# Temperature_humidity.net
KiCad netlist of a schematic drawn in Altium Designer
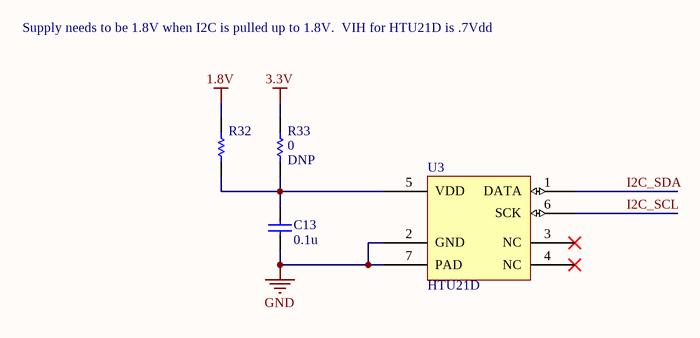
[diagram p0: Temperature_humidity.SchDoc]

(export (version "E")
  (design (tool "Eeschema 10.0.6"))
  (components
    (comp (ref "C13")
      (value "0.1u")
      (footprint "CAP0603")
      (description "CAP CER 0.1UF 50V 10% X7R 0603")
      (fields (field (name "TOLERANCE") "10%") (field (name "VOLTAGE") "50V"))
      (libsource (lib "Morpheus_pill") (part "C_0.1u_10_50_X7R_0603"))
    )
    (comp (ref "R32")
      (value "R_0_jumper_0.1_0402")
      (footprint "RES0402-SENSE-DVT")
      (description "RES SMD 0.0 OHM JUMPER 1/16W")
      (fields (field (name "TOLERANCE") "Jumper") (field (name "POWER") "1/16W"))
      (libsource (lib "Morpheus_pill") (part "R_0_jumper_0.1_0402"))
    )
    (comp (ref "R33")
      (value "DNP")
      (footprint "RES0402-SENSE-DVT")
      (description "RES SMD 0.0 OHM JUMPER 1/16W")
      (fields
        (field (name "ALTIUM_VALUE") "0")
        (field (name "TOLERANCE") "Jumper")
        (field (name "POWER") "1/16W")
      )
      (libsource (lib "Morpheus_pill") (part "R_0_jumper_0.1_0402"))
    )
    (comp (ref "U3")
      (value "HTU21D")
      (footprint "HTU2xx")
      (description "Meas-spec T/H sensor")
      (libsource (lib "Morpheus_pill") (part "HTU21D"))
    )
  )
  (nets
    (net (code "1") (name "/I2C_SCL") (class "Default")
      (node (ref "U3") (pin "6") (pinfunction "SCK_6") (pintype "bidirectional"))
    )
    (net (code "2") (name "/I2C_SDA") (class "Default")
      (node (ref "U3") (pin "1") (pinfunction "DATA_1") (pintype "bidirectional"))
    )
    (net (code "3") (name "1.8V") (class "Default")
      (node (ref "R32") (pin "2") (pinfunction "2_2") (pintype "passive"))
    )
    (net (code "4") (name "3.3V") (class "Default")
      (node (ref "R33") (pin "2") (pinfunction "2_2") (pintype "passive"))
    )
    (net (code "5") (name "GND") (class "Default")
      (node (ref "C13") (pin "1") (pinfunction "1_1") (pintype "passive"))
      (node (ref "U3") (pin "2") (pinfunction "GND_2") (pintype "power_in"))
      (node (ref "U3") (pin "7") (pinfunction "PAD_7") (pintype "passive"))
    )
    (net (code "6") (name "Net-(U3-VDD)") (class "Default")
      (node (ref "C13") (pin "2") (pinfunction "2_2") (pintype "passive"))
      (node (ref "R32") (pin "1") (pinfunction "1_1") (pintype "passive"))
      (node (ref "R33") (pin "1") (pinfunction "1_1") (pintype "passive"))
      (node (ref "U3") (pin "5") (pinfunction "VDD_5") (pintype "power_in"))
    )
    (net (code "7") (name "unconnected-(U3-NC-Pad3)") (class "Default")
      (node (ref "U3") (pin "3") (pinfunction "NC_3") (pintype "passive+no_connect"))
    )
    (net (code "8") (name "unconnected-(U3-NC-Pad4)") (class "Default")
      (node (ref "U3") (pin "4") (pinfunction "NC_4") (pintype "passive+no_connect"))
    )
  )
)
